# MeasuringCircuit_Hardware.net
KiCad netlist of a schematic drawn in EasyEDA Pro
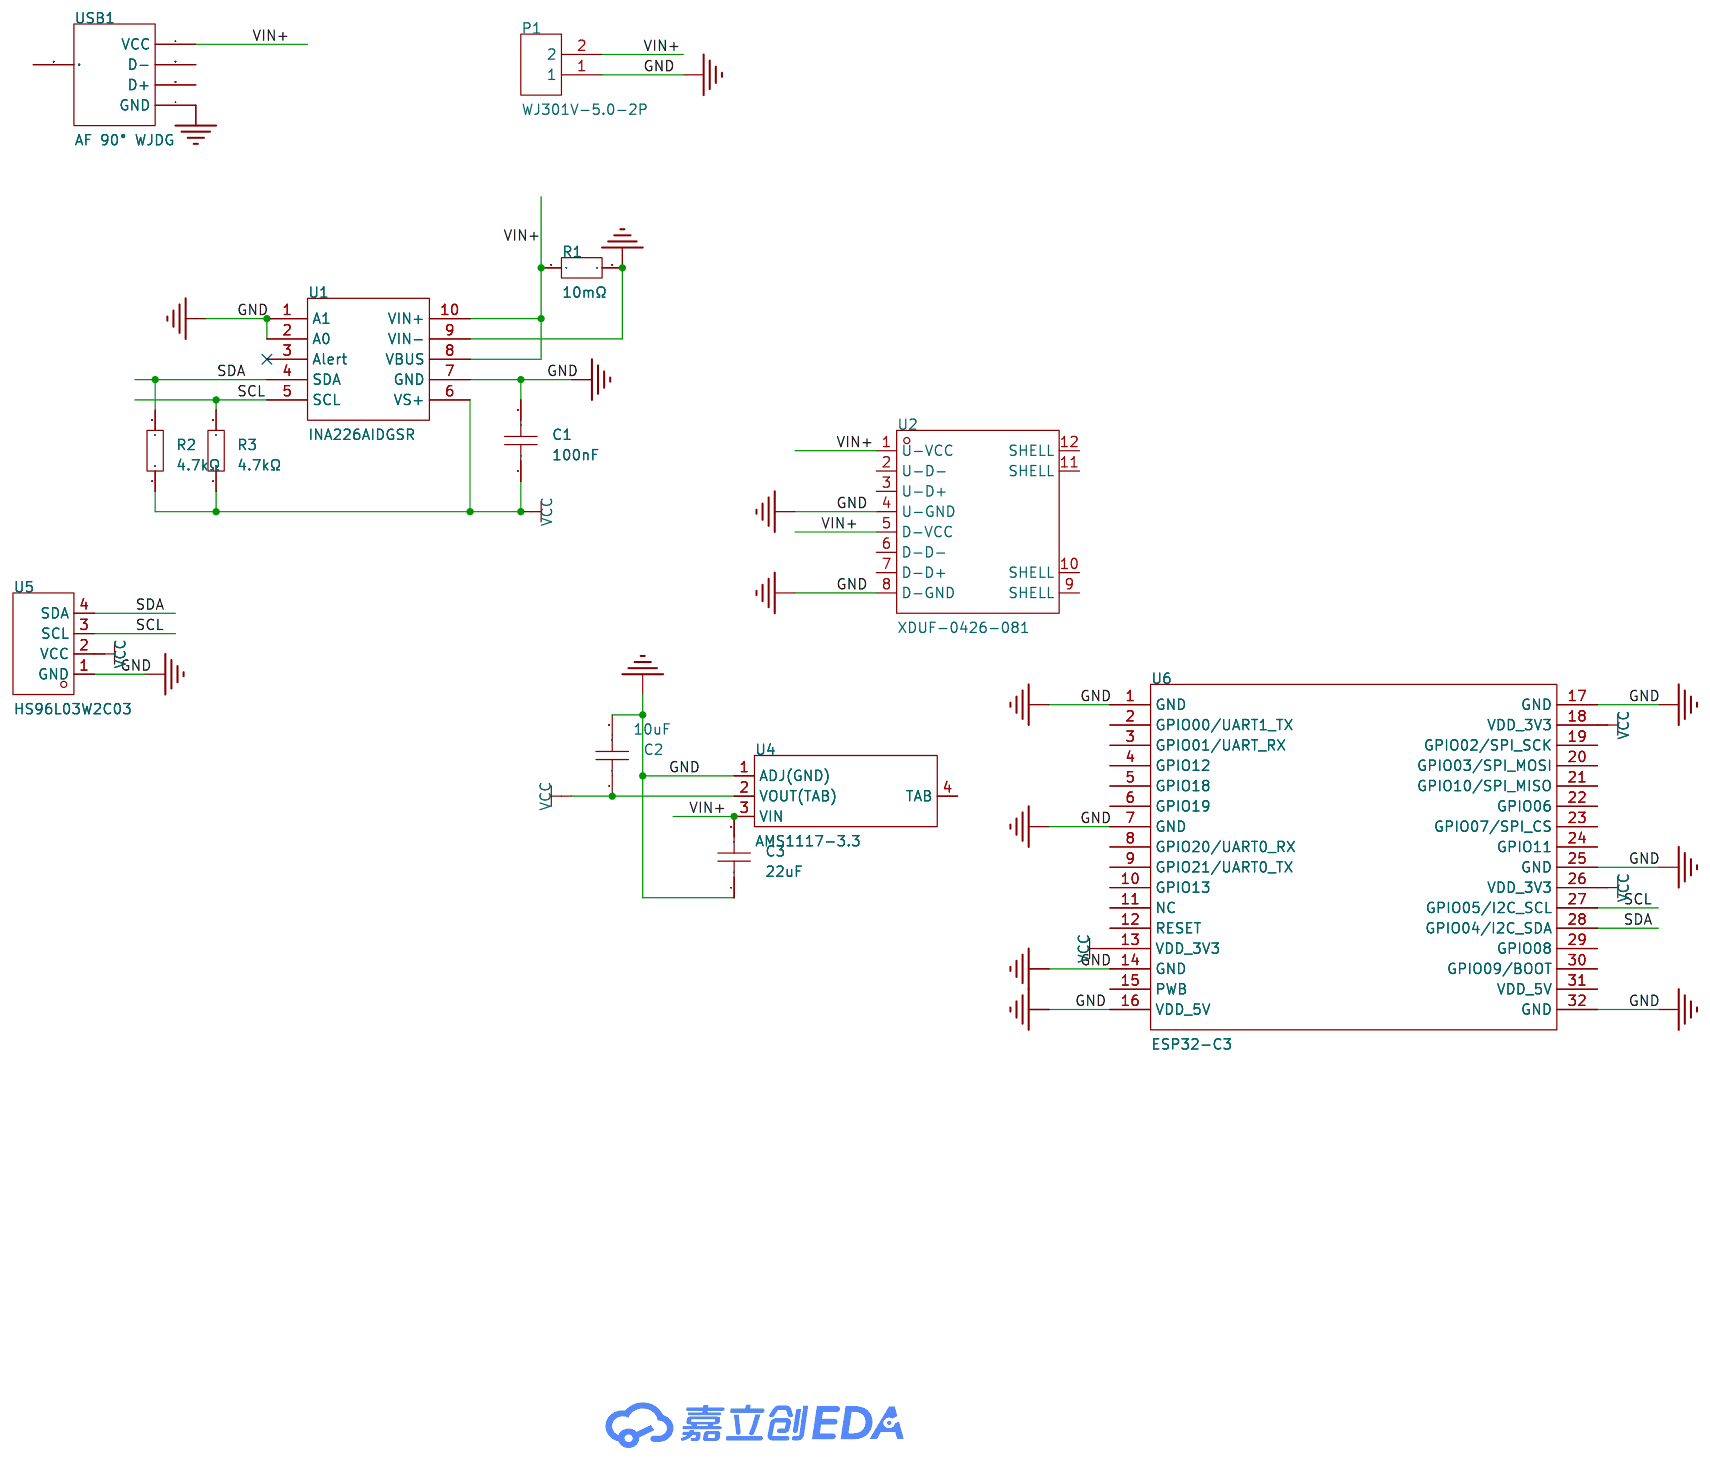
[diagram p0: schematic sheet]

(export (version "E")
  (design (tool "Eeschema 10.0.6"))
  (components
    (comp (ref "C1")
      (value "100nF")
      (footprint "easyedapro:C0603")
      (description "容值:100nF;精度:±10%;额定电压:50V;温度系数:X7R;")
      (fields
        (field (name "Manufacturer Part") "CC0603KRX7R9BB104")
        (field (name "Manufacturer") "YAGEO(国巨)")
      )
      (libsource (lib "easyedapro") (part "CC0603KRX7R9BB104"))
    )
    (comp (ref "C2")
      (value "10uF")
      (footprint "easyedapro:C0603")
      (description "容值:10uF;精度:±10%;额定电压:10V;温度系数:X5R;")
      (fields
        (field (name "Manufacturer Part") "CGA0603X5R106K100JT")
        (field (name "Manufacturer") "HRE(芯声)")
      )
      (libsource (lib "easyedapro") (part "CGA0603X5R106K100JT"))
    )
    (comp (ref "C3")
      (value "22uF")
      (footprint "easyedapro:C0603")
      (description "容值:22uF;精度:±20%;额定电压:16V;温度系数:X5R;")
      (fields
        (field (name "Manufacturer Part") "CGA0603X5R226M160JT")
        (field (name "Manufacturer") "HRE(芯声)")
      )
      (libsource (lib "easyedapro") (part "CGA0603X5R226M160JT"))
    )
    (comp (ref "P1")
      (value "WJ301V-5.0-2P")
      (footprint "easyedapro:CONN-TH_2P-P5.00_WJ301V-5.00-2P")
      (fields (field (name "Manufacturer") "KANGNEX(康奈克斯电气)"))
      (libsource (lib "easyedapro") (part "WJ301V-5.0-2P"))
    )
    (comp (ref "R1")
      (value "10mΩ")
      (footprint "easyedapro:R2512")
      (description "电阻类型:采样电阻;阻值:10mΩ;精度:±1%;额定压降:-;功率:3W;温度系数:±50ppm/°C;安装方式:贴片;")
      (fields (field (name "Manufacturer Part") "YLR12-3-10F-W") (field (name "Manufacturer") "yezhan(业展)"))
      (libsource (lib "easyedapro") (part "YLR12-3-10F-W"))
    )
    (comp (ref "R2")
      (value "4.7kΩ")
      (footprint "easyedapro:R0603")
      (description "电阻类型:厚膜电阻;阻值:4.7kΩ;精度:±1%;功率:100mW;最大工作电压:75V;温度系数:±100ppm/°C;")
      (fields
        (field (name "Manufacturer Part") "0603WAF4701T5E")
        (field (name "Manufacturer") "UNI-ROYAL(厚声)")
      )
      (libsource (lib "easyedapro") (part "0603WAF4701T5E"))
    )
    (comp (ref "R3")
      (value "4.7kΩ")
      (footprint "easyedapro:R0603")
      (description "电阻类型:厚膜电阻;阻值:4.7kΩ;精度:±1%;功率:100mW;最大工作电压:75V;温度系数:±100ppm/°C;")
      (fields
        (field (name "Manufacturer Part") "0603WAF4701T5E")
        (field (name "Manufacturer") "UNI-ROYAL(厚声)")
      )
      (libsource (lib "easyedapro") (part "0603WAF4701T5E"))
    )
    (comp (ref "U1")
      (value "INA226AIDGSR")
      (footprint "easyedapro:MSOP-10_L3.0-W3.0-P0.50-LS5.0-BL")
      (description "放大器数:-;共模电压:300mV~40V;增益:-;带宽:-;")
      (fields (field (name "Manufacturer") "TI(德州仪器)"))
      (libsource (lib "easyedapro") (part "INA226AIDGSR"))
    )
    (comp (ref "U2")
      (value "XDUF-0426-081")
      (footprint "easyedapro:USB-A-TH_XDUF-0426-081")
      (description "连接器类型:Type-A;标准:USB 2.0;公母:母;安装方式:弯插;触点数量:8P;端口数量:2;额定电流 - 电源:3A;触头材质:-;触头镀层:金;工作温度范围:-40°C~+85°C;")
      (fields (field (name "Manufacturer") "LX(连欣科技)"))
      (libsource (lib "easyedapro") (part "XDUF-0426-081_C18202150"))
    )
    (comp (ref "U4")
      (value "AMS1117-3.3")
      (footprint "easyedapro:SOT-223-4_L6.5-W3.5-P2.30-LS7.0-BR")
      (description "输出类型:固定;工作电压:12V;输出电压:3.3V;输出电流:1A;电源纹波抑制比(PSRR):60dB@(120Hz);输出极性:正极;")
      (fields (field (name "Manufacturer") "UMW(友台半导体)"))
      (libsource (lib "easyedapro") (part "AMS1117-3.3_C347222"))
    )
    (comp (ref "U5")
      (value "HS96L03W2C03")
      (footprint "easyedapro:OLED-TH_L27.8-W27.2-P2.54_C9900033791")
      (description "主控芯片:SSD1315;接口类型:I2C;尺寸(inch):0.96;像素分辨率:128x64;")
      (fields (field (name "Manufacturer") "HS(汉昇)"))
      (libsource (lib "easyedapro") (part "HS96L03W2C03"))
    )
    (comp (ref "U6") (value "ESP32-C3") (libsource (lib "easyedapro") (part "ESP32-C3")))
    (comp (ref "USB1")
      (value "AF 90° WJDG")
      (footprint "easyedapro:USB-A-TH_AF-WJDG")
      (description "连接器类型:Type-A;标准:USB 2.0;公母:母;安装方式:弯插;触点数量:4P;端口数量:1;额定电流 - 电源:1.5A;工作温度范围:-25°C~+85°C;")
      (fields (field (name "Manufacturer") "SHOU HAN(首韩)"))
      (libsource (lib "easyedapro") (part "AF 90° WJDG"))
    )
  )
  (nets
    (net (code "1") (name "/SCL") (class "Default")
      (node (ref "R3") (pin "2") (pinfunction "2_2") (pintype "input"))
      (node (ref "U1") (pin "5") (pinfunction "SCL_5") (pintype "unspecified"))
      (node (ref "U5") (pin "3") (pinfunction "SCL_3") (pintype "unspecified"))
      (node (ref "U6") (pin "27") (pinfunction "GPIO05/I2C_SCL_27") (pintype "input"))
    )
    (net (code "2") (name "/SDA") (class "Default")
      (node (ref "R2") (pin "2") (pinfunction "2_2") (pintype "input"))
      (node (ref "U1") (pin "4") (pinfunction "SDA_4") (pintype "unspecified"))
      (node (ref "U5") (pin "4") (pinfunction "SDA_4") (pintype "unspecified"))
      (node (ref "U6") (pin "28") (pinfunction "GPIO04/I2C_SDA_28") (pintype "input"))
    )
    (net (code "3") (name "/VIN+") (class "Default")
      (node (ref "C3") (pin "2") (pinfunction "2_2") (pintype "unspecified"))
      (node (ref "P1") (pin "2") (pinfunction "2_2") (pintype "unspecified"))
      (node (ref "R1") (pin "2") (pinfunction "2_2") (pintype "unspecified"))
      (node (ref "U1") (pin "10") (pinfunction "VIN+_10") (pintype "unspecified"))
      (node (ref "U1") (pin "8") (pinfunction "VBUS_8") (pintype "unspecified"))
      (node (ref "U2") (pin "1") (pinfunction "U-VCC_1") (pintype "unspecified"))
      (node (ref "U2") (pin "5") (pinfunction "D-VCC_5") (pintype "unspecified"))
      (node (ref "U4") (pin "3") (pinfunction "VIN_3") (pintype "unspecified"))
      (node (ref "USB1") (pin "1") (pinfunction "VCC_1") (pintype "input"))
    )
    (net (code "4") (name "GND") (class "Default")
      (node (ref "C1") (pin "2") (pinfunction "2_2") (pintype "unspecified"))
      (node (ref "C2") (pin "2") (pinfunction "2_2") (pintype "unspecified"))
      (node (ref "C3") (pin "1") (pinfunction "1_1") (pintype "unspecified"))
      (node (ref "P1") (pin "1") (pinfunction "1_1") (pintype "unspecified"))
      (node (ref "R1") (pin "1") (pinfunction "1_1") (pintype "unspecified"))
      (node (ref "U1") (pin "1") (pinfunction "A1_1") (pintype "unspecified"))
      (node (ref "U1") (pin "2") (pinfunction "A0_2") (pintype "unspecified"))
      (node (ref "U1") (pin "7") (pinfunction "GND_7") (pintype "unspecified"))
      (node (ref "U1") (pin "9") (pinfunction "VIN-_9") (pintype "unspecified"))
      (node (ref "U2") (pin "4") (pinfunction "U-GND_4") (pintype "unspecified"))
      (node (ref "U2") (pin "8") (pinfunction "D-GND_8") (pintype "unspecified"))
      (node (ref "U4") (pin "1") (pinfunction "ADJ(GND)_1") (pintype "unspecified"))
      (node (ref "U5") (pin "1") (pinfunction "GND_1") (pintype "unspecified"))
      (node (ref "U6") (pin "1") (pinfunction "GND_1") (pintype "input"))
      (node (ref "U6") (pin "14") (pinfunction "GND_14") (pintype "input"))
      (node (ref "U6") (pin "16") (pinfunction "VDD_5V_16") (pintype "input"))
      (node (ref "U6") (pin "17") (pinfunction "GND_17") (pintype "input"))
      (node (ref "U6") (pin "25") (pinfunction "GND_25") (pintype "input"))
      (node (ref "U6") (pin "32") (pinfunction "GND_32") (pintype "input"))
      (node (ref "U6") (pin "7") (pinfunction "GND_7") (pintype "input"))
      (node (ref "USB1") (pin "4") (pinfunction "GND_4") (pintype "input"))
    )
    (net (code "5") (name "VCC") (class "Default")
      (node (ref "C1") (pin "1") (pinfunction "1_1") (pintype "unspecified"))
      (node (ref "C2") (pin "1") (pinfunction "1_1") (pintype "unspecified"))
      (node (ref "R2") (pin "1") (pinfunction "1_1") (pintype "input"))
      (node (ref "R3") (pin "1") (pinfunction "1_1") (pintype "input"))
      (node (ref "U1") (pin "6") (pinfunction "VS+_6") (pintype "unspecified"))
      (node (ref "U4") (pin "2") (pinfunction "VOUT(TAB)_2") (pintype "unspecified"))
      (node (ref "U5") (pin "2") (pinfunction "VCC_2") (pintype "unspecified"))
      (node (ref "U6") (pin "13") (pinfunction "VDD_3V3_13") (pintype "input"))
      (node (ref "U6") (pin "18") (pinfunction "VDD_3V3_18") (pintype "input"))
      (node (ref "U6") (pin "26") (pinfunction "VDD_3V3_26") (pintype "input"))
    )
    (net (code "6") (name "unconnected-(U1-Alert-Pad3)") (class "Default")
      (node (ref "U1") (pin "3") (pinfunction "Alert_3") (pintype "unspecified+no_connect"))
    )
    (net (code "7") (name "unconnected-(U2-D-D+-Pad7)") (class "Default")
      (node (ref "U2") (pin "7") (pinfunction "D-D+_7") (pintype "unspecified"))
    )
    (net (code "8") (name "unconnected-(U2-D-D--Pad6)") (class "Default")
      (node (ref "U2") (pin "6") (pinfunction "D-D-_6") (pintype "unspecified"))
    )
    (net (code "9") (name "unconnected-(U2-SHELL-Pad9)") (class "Default")
      (node (ref "U2") (pin "9") (pinfunction "SHELL_9") (pintype "unspecified"))
    )
    (net (code "10") (name "unconnected-(U2-SHELL-Pad10)") (class "Default")
      (node (ref "U2") (pin "10") (pinfunction "SHELL_10") (pintype "unspecified"))
    )
    (net (code "11") (name "unconnected-(U2-SHELL-Pad11)") (class "Default")
      (node (ref "U2") (pin "11") (pinfunction "SHELL_11") (pintype "unspecified"))
    )
    (net (code "12") (name "unconnected-(U2-SHELL-Pad12)") (class "Default")
      (node (ref "U2") (pin "12") (pinfunction "SHELL_12") (pintype "unspecified"))
    )
    (net (code "13") (name "unconnected-(U2-U-D+-Pad3)") (class "Default")
      (node (ref "U2") (pin "3") (pinfunction "U-D+_3") (pintype "unspecified"))
    )
    (net (code "14") (name "unconnected-(U2-U-D--Pad2)") (class "Default")
      (node (ref "U2") (pin "2") (pinfunction "U-D-_2") (pintype "unspecified"))
    )
    (net (code "15") (name "unconnected-(U4-TAB-Pad4)") (class "Default")
      (node (ref "U4") (pin "4") (pinfunction "TAB_4") (pintype "unspecified"))
    )
    (net (code "16") (name "unconnected-(U6-GPIO00{slash}UART1_TX-Pad2)") (class "Default")
      (node (ref "U6") (pin "2") (pinfunction "GPIO00/UART1_TX_2") (pintype "input"))
    )
    (net (code "17") (name "unconnected-(U6-GPIO01{slash}UART_RX-Pad3)") (class "Default")
      (node (ref "U6") (pin "3") (pinfunction "GPIO01/UART_RX_3") (pintype "input"))
    )
    (net (code "18") (name "unconnected-(U6-GPIO02{slash}SPI_SCK-Pad19)") (class "Default")
      (node (ref "U6") (pin "19") (pinfunction "GPIO02/SPI_SCK_19") (pintype "input"))
    )
    (net (code "19") (name "unconnected-(U6-GPIO03{slash}SPI_MOSI-Pad20)") (class "Default")
      (node (ref "U6") (pin "20") (pinfunction "GPIO03/SPI_MOSI_20") (pintype "input"))
    )
    (net (code "20") (name "unconnected-(U6-GPIO06-Pad22)") (class "Default")
      (node (ref "U6") (pin "22") (pinfunction "GPIO06_22") (pintype "input"))
    )
    (net (code "21") (name "unconnected-(U6-GPIO07{slash}SPI_CS-Pad23)") (class "Default")
      (node (ref "U6") (pin "23") (pinfunction "GPIO07/SPI_CS_23") (pintype "input"))
    )
    (net (code "22") (name "unconnected-(U6-GPIO08-Pad29)") (class "Default")
      (node (ref "U6") (pin "29") (pinfunction "GPIO08_29") (pintype "input"))
    )
    (net (code "23") (name "unconnected-(U6-GPIO09{slash}BOOT-Pad30)") (class "Default")
      (node (ref "U6") (pin "30") (pinfunction "GPIO09/BOOT_30") (pintype "input"))
    )
    (net (code "24") (name "unconnected-(U6-GPIO10{slash}SPI_MISO-Pad21)") (class "Default")
      (node (ref "U6") (pin "21") (pinfunction "GPIO10/SPI_MISO_21") (pintype "input"))
    )
    (net (code "25") (name "unconnected-(U6-GPIO11-Pad24)") (class "Default")
      (node (ref "U6") (pin "24") (pinfunction "GPIO11_24") (pintype "input"))
    )
    (net (code "26") (name "unconnected-(U6-GPIO12-Pad4)") (class "Default")
      (node (ref "U6") (pin "4") (pinfunction "GPIO12_4") (pintype "input"))
    )
    (net (code "27") (name "unconnected-(U6-GPIO13-Pad10)") (class "Default")
      (node (ref "U6") (pin "10") (pinfunction "GPIO13_10") (pintype "input"))
    )
    (net (code "28") (name "unconnected-(U6-GPIO18-Pad5)") (class "Default")
      (node (ref "U6") (pin "5") (pinfunction "GPIO18_5") (pintype "input"))
    )
    (net (code "29") (name "unconnected-(U6-GPIO19-Pad6)") (class "Default")
      (node (ref "U6") (pin "6") (pinfunction "GPIO19_6") (pintype "input"))
    )
    (net (code "30") (name "unconnected-(U6-GPIO20{slash}UART0_RX-Pad8)") (class "Default")
      (node (ref "U6") (pin "8") (pinfunction "GPIO20/UART0_RX_8") (pintype "input"))
    )
    (net (code "31") (name "unconnected-(U6-GPIO21{slash}UART0_TX-Pad9)") (class "Default")
      (node (ref "U6") (pin "9") (pinfunction "GPIO21/UART0_TX_9") (pintype "input"))
    )
    (net (code "32") (name "unconnected-(U6-NC-Pad11)") (class "Default")
      (node (ref "U6") (pin "11") (pinfunction "NC_11") (pintype "input"))
    )
    (net (code "33") (name "unconnected-(U6-PWB-Pad15)") (class "Default")
      (node (ref "U6") (pin "15") (pinfunction "PWB_15") (pintype "input"))
    )
    (net (code "34") (name "unconnected-(U6-RESET-Pad12)") (class "Default")
      (node (ref "U6") (pin "12") (pinfunction "RESET_12") (pintype "input"))
    )
    (net (code "35") (name "unconnected-(U6-VDD_5V-Pad31)") (class "Default")
      (node (ref "U6") (pin "31") (pinfunction "VDD_5V_31") (pintype "input"))
    )
    (net (code "36") (name "unconnected-(USB1-D+-Pad3)") (class "Default")
      (node (ref "USB1") (pin "3") (pinfunction "D+_3") (pintype "input"))
    )
    (net (code "37") (name "unconnected-(USB1-D--Pad2)") (class "Default")
      (node (ref "USB1") (pin "2") (pinfunction "D-_2") (pintype "input"))
    )
    (net (code "38") (name "unconnected-(USB1-SHLD-Pad5)") (class "Default")
      (node (ref "USB1") (pin "5") (pinfunction "SHLD_5") (pintype "unspecified"))
    )
  )
)
